# audio.net
KiCad netlist of a schematic drawn in Altium Designer
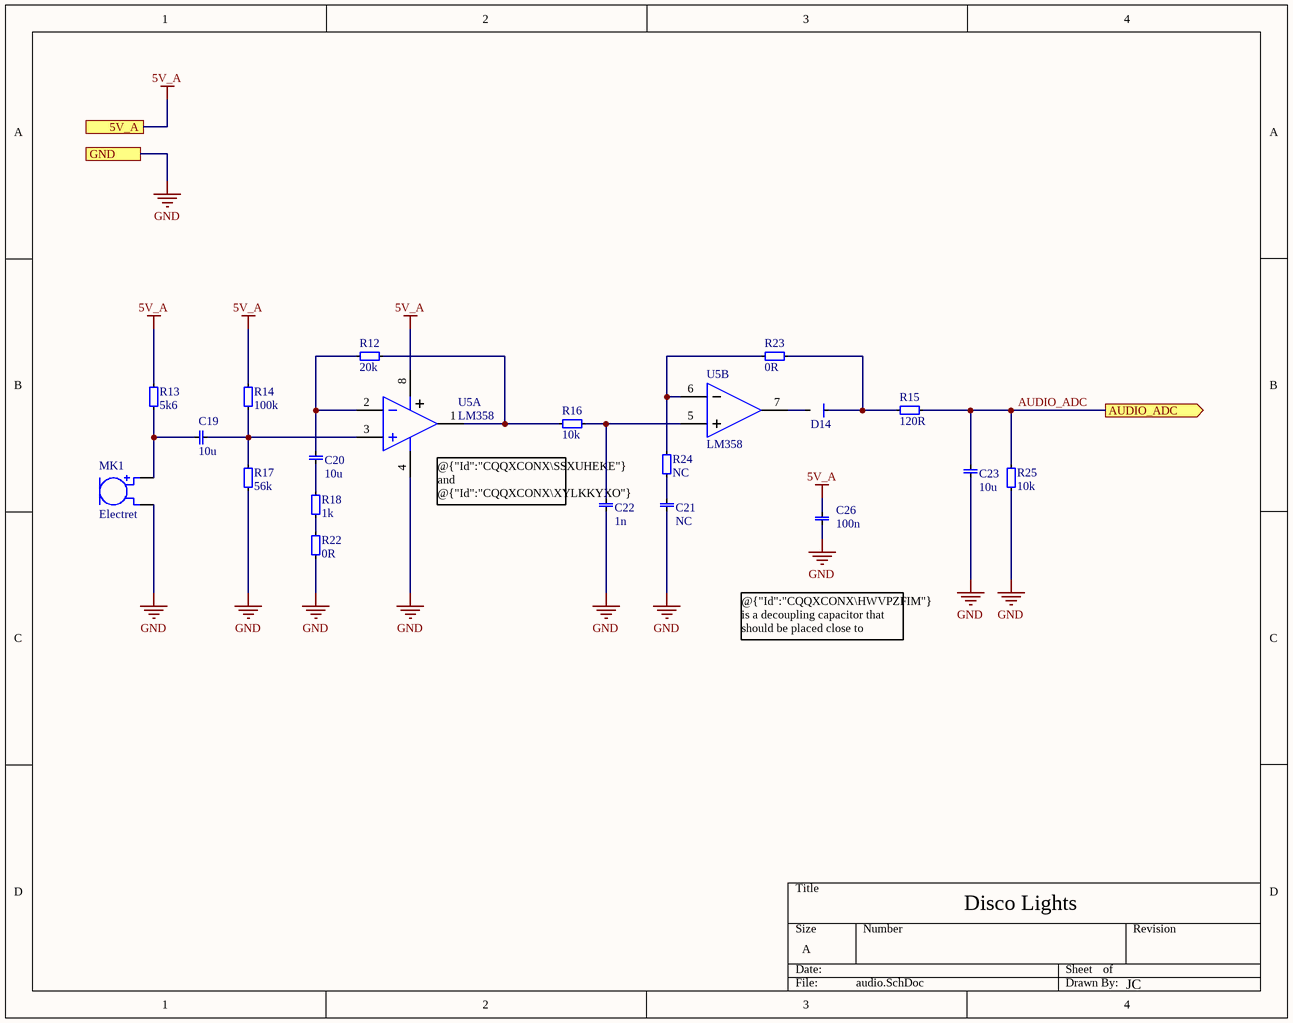
[diagram p0: audio.SchDoc]

(export (version "E")
  (design (tool "Eeschema 10.0.6"))
  (components
    (comp (ref "C19")
      (value "10u")
      (footprint "0603 cap")
      (fields
        (field (name "JLCPCB PART #") "C386081")
        (field (name "MANUFACTURER PART NUMBER") "TMK107BBJ106MA-T")
        (field (name "Comment") "0603, capacitor")
      )
      (libsource (lib "jclib") (part "0603, capacitor"))
    )
    (comp (ref "C20")
      (value "10u")
      (footprint "0603 cap")
      (fields
        (field (name "JLCPCB PART #") "C386081")
        (field (name "MANUFACTURER PART NUMBER") "TMK107BBJ106MA-T")
        (field (name "Comment") "0603, capacitor")
      )
      (libsource (lib "jclib") (part "0603, capacitor"))
    )
    (comp (ref "C21")
      (value "NC")
      (footprint "0603 cap")
      (fields (field (name "Comment") "0603, capacitor"))
      (libsource (lib "jclib") (part "0603, capacitor"))
    )
    (comp (ref "C22")
      (value "1n")
      (footprint "0603 cap")
      (fields
        (field (name "JLCPCB PART #") "C100040")
        (field (name "MANUFACTURER PART NUMBER") "CC0603KRX7R9BB102")
        (field (name "Comment") "0603, capacitor")
      )
      (libsource (lib "jclib") (part "0603, capacitor"))
    )
    (comp (ref "C23")
      (value "10u")
      (footprint "0603 cap")
      (fields
        (field (name "JLCPCB PART #") "C386081")
        (field (name "MANUFACTURER PART NUMBER") "TMK107BBJ106MA-T")
        (field (name "Comment") "0603, capacitor")
      )
      (libsource (lib "jclib") (part "0603, capacitor"))
    )
    (comp (ref "C26")
      (value "100n")
      (footprint "0603 cap")
      (fields
        (field (name "JLCPCB PART #") "C14663")
        (field (name "MANUFACTURER PART NUMBER") "CC0603KRX7R9BB102")
        (field (name "Comment") "0603, capacitor")
      )
      (libsource (lib "jclib") (part "0603, capacitor"))
    )
    (comp (ref "D14")
      (value "Diode, SMD")
      (footprint "SOD323")
      (fields (field (name "JLCPCB PART #") "C117941") (field (name "MANUFACTURER PART NUMBER") "BAT760,115"))
      (libsource (lib "jclib") (part "Diode, SMD"))
    )
    (comp (ref "MK1")
      (value "Electret")
      (footprint "ElectretMic_9.7mm_6.7mm")
      (description "D9.7mm H6.7mm, Electrokit art nr: 40290007")
      (libsource (lib "jclib") (part "Electret Mic"))
    )
    (comp (ref "R12")
      (value "20k")
      (footprint "0603")
      (fields
        (field (name "JLCPCB PART #") "C723637")
        (field (name "MANUFACTURER PART NUMBER") "RT0603BRD0720KL")
        (field (name "Comment") "0603, resistor")
      )
      (libsource (lib "jclib") (part "0603, resistor"))
    )
    (comp (ref "R13")
      (value "5k6")
      (footprint "0603")
      (fields
        (field (name "JLCPCB PART #") "C138278")
        (field (name "MANUFACTURER PART NUMBER") "AC0603FR-075K6L")
        (field (name "Comment") "0603, resistor")
      )
      (libsource (lib "jclib") (part "0603, resistor"))
    )
    (comp (ref "R14")
      (value "100k")
      (footprint "0603")
      (fields
        (field (name "JLCPCB PART #") "C14675")
        (field (name "MANUFACTURER PART NUMBER") "RC0603FR-07100KL")
        (field (name "Comment") "0603, resistor")
      )
      (libsource (lib "jclib") (part "0603, resistor"))
    )
    (comp (ref "R15")
      (value "120R")
      (footprint "0603")
      (fields
        (field (name "JLCPCB PART #") "C114681")
        (field (name "MANUFACTURER PART NUMBER") "RC0603JR-07120RL")
        (field (name "Comment") "0603, resistor")
      )
      (libsource (lib "jclib") (part "0603, resistor"))
    )
    (comp (ref "R16")
      (value "10k")
      (footprint "0603")
      (fields
        (field (name "JLCPCB PART #") "C98220")
        (field (name "MANUFACTURER PART NUMBER") "RC0603FR-0710KL")
        (field (name "Comment") "0603, resistor")
      )
      (libsource (lib "jclib") (part "0603, resistor"))
    )
    (comp (ref "R17")
      (value "56k")
      (footprint "0603")
      (fields
        (field (name "JLCPCB PART #") "C114630")
        (field (name "MANUFACTURER PART NUMBER") "C3216X7R1C106KT000N")
        (field (name "Comment") "0603, resistor")
      )
      (libsource (lib "jclib") (part "0603, resistor"))
    )
    (comp (ref "R18")
      (value "1k")
      (footprint "0603")
      (fields
        (field (name "JLCPCB PART #") "C203217")
        (field (name "MANUFACTURER PART NUMBER") "CR0603-FX-1001ELF")
        (field (name "Comment") "0603, resistor")
      )
      (libsource (lib "jclib") (part "0603, resistor"))
    )
    (comp (ref "R22")
      (value "0R")
      (footprint "0603")
      (fields
        (field (name "JLCPCB PART #") "C95177")
        (field (name "MANUFACTURER PART NUMBER") "RC0603JR-070RL")
        (field (name "Comment") "0603, resistor")
      )
      (libsource (lib "jclib") (part "0603, resistor"))
    )
    (comp (ref "R23")
      (value "0R")
      (footprint "0603")
      (fields
        (field (name "JLCPCB PART #") "C95177")
        (field (name "MANUFACTURER PART NUMBER") "RC0603JR-070RL")
        (field (name "Comment") "0603, resistor")
      )
      (libsource (lib "jclib") (part "0603, resistor"))
    )
    (comp (ref "R24")
      (value "NC")
      (footprint "0603")
      (fields (field (name "Comment") "0603, resistor"))
      (libsource (lib "jclib") (part "0603, resistor"))
    )
    (comp (ref "R25")
      (value "10k")
      (footprint "0603")
      (fields
        (field (name "JLCPCB PART #") "C98220")
        (field (name "MANUFACTURER PART NUMBER") "RC0603FR-0710KL")
        (field (name "Comment") "0603, resistor")
      )
      (libsource (lib "jclib") (part "0603, resistor"))
    )
    (comp (ref "U5")
      (value "LM358")
      (footprint "SOIC8")
      (description "Dual FET-Input Operational Amplifier")
      (libsource (lib "jclib") (part "LM358"))
    )
  )
  (nets
    (net (code "1") (name "/AUDIO_ADC") (class "Default")
      (node (ref "C23") (pin "0") (pinfunction "0_0") (pintype "passive"))
      (node (ref "R15") (pin "1") (pinfunction "1_1") (pintype "passive"))
      (node (ref "R25") (pin "0") (pinfunction "0_0") (pintype "passive"))
    )
    (net (code "2") (name "5V_A") (class "Default")
      (node (ref "C26") (pin "1") (pinfunction "1_1") (pintype "passive"))
      (node (ref "R13") (pin "0") (pinfunction "0_0") (pintype "passive"))
      (node (ref "R14") (pin "0") (pinfunction "0_0") (pintype "passive"))
      (node (ref "U5") (pin "8") (pinfunction "V+_8") (pintype "power_in"))
    )
    (net (code "3") (name "GND") (class "Default")
      (node (ref "C21") (pin "0") (pinfunction "0_0") (pintype "passive"))
      (node (ref "C22") (pin "0") (pinfunction "0_0") (pintype "passive"))
      (node (ref "C23") (pin "1") (pinfunction "1_1") (pintype "passive"))
      (node (ref "C26") (pin "0") (pinfunction "0_0") (pintype "passive"))
      (node (ref "MK1") (pin "2") (pinfunction "2_2") (pintype "passive"))
      (node (ref "R17") (pin "1") (pinfunction "1_1") (pintype "passive"))
      (node (ref "R22") (pin "0") (pinfunction "0_0") (pintype "passive"))
      (node (ref "R25") (pin "1") (pinfunction "1_1") (pintype "passive"))
      (node (ref "U5") (pin "4") (pinfunction "V-_4") (pintype "power_in"))
    )
    (net (code "4") (name "Net-(C19-Pad1)") (class "Default")
      (node (ref "C19") (pin "1") (pinfunction "1_1") (pintype "passive"))
      (node (ref "MK1") (pin "1") (pinfunction "1_1") (pintype "passive"))
      (node (ref "R13") (pin "1") (pinfunction "1_1") (pintype "passive"))
    )
    (net (code "5") (name "Net-(C20-Pad0)") (class "Default")
      (node (ref "C20") (pin "0") (pinfunction "0_0") (pintype "passive"))
      (node (ref "R18") (pin "0") (pinfunction "0_0") (pintype "passive"))
    )
    (net (code "6") (name "Net-(C21-Pad1)") (class "Default")
      (node (ref "C21") (pin "1") (pinfunction "1_1") (pintype "passive"))
      (node (ref "R24") (pin "1") (pinfunction "1_1") (pintype "passive"))
    )
    (net (code "7") (name "Net-(D14-Pad1)") (class "Default")
      (node (ref "D14") (pin "1") (pinfunction "1_1") (pintype "passive"))
      (node (ref "R15") (pin "0") (pinfunction "0_0") (pintype "passive"))
      (node (ref "R23") (pin "1") (pinfunction "1_1") (pintype "passive"))
    )
    (net (code "8") (name "Net-(R18-Pad1)") (class "Default")
      (node (ref "R18") (pin "1") (pinfunction "1_1") (pintype "passive"))
      (node (ref "R22") (pin "1") (pinfunction "1_1") (pintype "passive"))
    )
    (net (code "9") (name "Net-(U5A-IN+)") (class "Default")
      (node (ref "C19") (pin "0") (pinfunction "0_0") (pintype "passive"))
      (node (ref "R14") (pin "1") (pinfunction "1_1") (pintype "passive"))
      (node (ref "R17") (pin "0") (pinfunction "0_0") (pintype "passive"))
      (node (ref "U5") (pin "3") (pinfunction "IN+_3") (pintype "passive"))
    )
    (net (code "10") (name "Net-(U5A-IN-)") (class "Default")
      (node (ref "C20") (pin "1") (pinfunction "1_1") (pintype "passive"))
      (node (ref "R12") (pin "0") (pinfunction "0_0") (pintype "passive"))
      (node (ref "U5") (pin "2") (pinfunction "IN-_2") (pintype "passive"))
    )
    (net (code "11") (name "Net-(U5A-OUT1)") (class "Default")
      (node (ref "R12") (pin "1") (pinfunction "1_1") (pintype "passive"))
      (node (ref "R16") (pin "0") (pinfunction "0_0") (pintype "passive"))
      (node (ref "U5") (pin "1") (pinfunction "OUT1_1") (pintype "passive"))
    )
    (net (code "12") (name "Net-(U5B-IN+)") (class "Default")
      (node (ref "C22") (pin "1") (pinfunction "1_1") (pintype "passive"))
      (node (ref "R16") (pin "1") (pinfunction "1_1") (pintype "passive"))
      (node (ref "U5") (pin "5") (pinfunction "IN+_5") (pintype "passive"))
    )
    (net (code "13") (name "Net-(U5B-IN-)") (class "Default")
      (node (ref "R23") (pin "0") (pinfunction "0_0") (pintype "passive"))
      (node (ref "R24") (pin "0") (pinfunction "0_0") (pintype "passive"))
      (node (ref "U5") (pin "6") (pinfunction "IN-_6") (pintype "passive"))
    )
    (net (code "14") (name "Net-(U5B-OUT2)") (class "Default")
      (node (ref "D14") (pin "2") (pinfunction "2_2") (pintype "passive"))
      (node (ref "U5") (pin "7") (pinfunction "OUT2_7") (pintype "passive"))
    )
  )
)
